# 0_EPS_Interface.net
KiCad netlist of a schematic drawn in Altium Designer
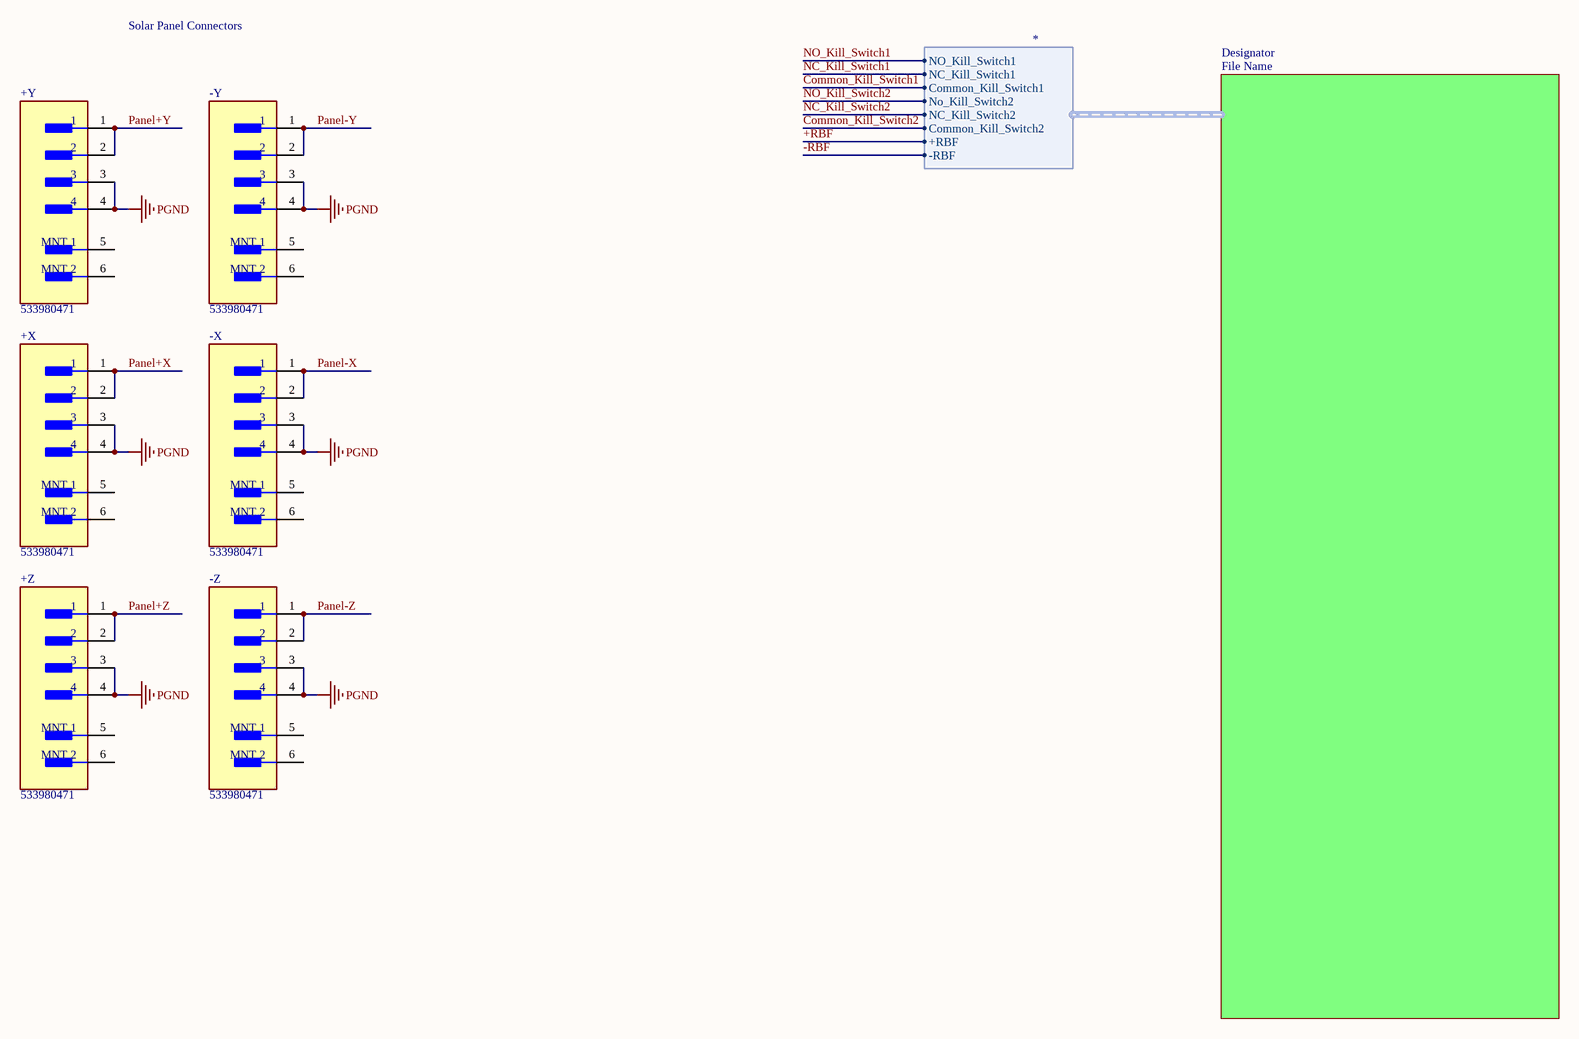
[diagram p0: 0_EPS_Interface.SchDoc]

(export (version "E")
  (design (tool "Eeschema 10.0.6"))
  (components
    (comp (ref "+X")
      (value "533980471")
      (footprint "FP-533980471-MFG")
      (description "Connector Header Surface Mount 4 position 0.049\" (1.25mm)")
      (fields (field (name "OCTOPART") "https://octopart.com/53398-0471-molex-655296"))
      (libsource (lib "Altium Content Vault") (part "3b6f738a5616415d78381ad43816e4a"))
    )
    (comp (ref "+Y")
      (value "533980471")
      (footprint "FP-533980471-MFG")
      (description "Connector Header Surface Mount 4 position 0.049\" (1.25mm)")
      (fields (field (name "OCTOPART") "https://octopart.com/53398-0471-molex-655296"))
      (libsource (lib "Altium Content Vault") (part "3b6f738a5616415d78381ad43816e4a"))
    )
    (comp (ref "+Z")
      (value "533980471")
      (footprint "FP-533980471-MFG")
      (description "Connector Header Surface Mount 4 position 0.049\" (1.25mm)")
      (fields (field (name "OCTOPART") "https://octopart.com/53398-0471-molex-655296"))
      (libsource (lib "Altium Content Vault") (part "3b6f738a5616415d78381ad43816e4a"))
    )
    (comp (ref "-X")
      (value "533980471")
      (footprint "FP-533980471-MFG")
      (description "Connector Header Surface Mount 4 position 0.049\" (1.25mm)")
      (fields (field (name "OCTOPART") "https://octopart.com/53398-0471-molex-655296"))
      (libsource (lib "Altium Content Vault") (part "3b6f738a5616415d78381ad43816e4a"))
    )
    (comp (ref "-Y")
      (value "533980471")
      (footprint "FP-533980471-MFG")
      (description "Connector Header Surface Mount 4 position 0.049\" (1.25mm)")
      (fields (field (name "OCTOPART") "https://octopart.com/53398-0471-molex-655296"))
      (libsource (lib "Altium Content Vault") (part "3b6f738a5616415d78381ad43816e4a"))
    )
    (comp (ref "-Z")
      (value "533980471")
      (footprint "FP-533980471-MFG")
      (description "Connector Header Surface Mount 4 position 0.049\" (1.25mm)")
      (fields (field (name "OCTOPART") "https://octopart.com/53398-0471-molex-655296"))
      (libsource (lib "Altium Content Vault") (part "3b6f738a5616415d78381ad43816e4a"))
    )
  )
  (nets
    (net (code "10") (name "/Panel+X") (class "Default")
      (node (ref "+X") (pin "1") (pinfunction "1_1") (pintype "passive"))
      (node (ref "+X") (pin "2") (pinfunction "2_2") (pintype "passive"))
    )
    (net (code "11") (name "/Panel+Y") (class "Default")
      (node (ref "+Y") (pin "1") (pinfunction "1_1") (pintype "passive"))
      (node (ref "+Y") (pin "2") (pinfunction "2_2") (pintype "passive"))
    )
    (net (code "12") (name "/Panel+Z") (class "Default")
      (node (ref "+Z") (pin "1") (pinfunction "1_1") (pintype "passive"))
      (node (ref "+Z") (pin "2") (pinfunction "2_2") (pintype "passive"))
    )
    (net (code "13") (name "/Panel-X") (class "Default")
      (node (ref "-X") (pin "1") (pinfunction "1_1") (pintype "passive"))
      (node (ref "-X") (pin "2") (pinfunction "2_2") (pintype "passive"))
    )
    (net (code "14") (name "/Panel-Y") (class "Default")
      (node (ref "-Y") (pin "1") (pinfunction "1_1") (pintype "passive"))
      (node (ref "-Y") (pin "2") (pinfunction "2_2") (pintype "passive"))
    )
    (net (code "15") (name "/Panel-Z") (class "Default")
      (node (ref "-Z") (pin "1") (pinfunction "1_1") (pintype "passive"))
      (node (ref "-Z") (pin "2") (pinfunction "2_2") (pintype "passive"))
    )
    (net (code "17") (name "PGND") (class "Default")
      (node (ref "+X") (pin "3") (pinfunction "3_3") (pintype "passive"))
      (node (ref "+X") (pin "4") (pinfunction "4_4") (pintype "passive"))
      (node (ref "+Y") (pin "3") (pinfunction "3_3") (pintype "passive"))
      (node (ref "+Y") (pin "4") (pinfunction "4_4") (pintype "passive"))
      (node (ref "+Z") (pin "3") (pinfunction "3_3") (pintype "passive"))
      (node (ref "+Z") (pin "4") (pinfunction "4_4") (pintype "passive"))
      (node (ref "-X") (pin "3") (pinfunction "3_3") (pintype "passive"))
      (node (ref "-X") (pin "4") (pinfunction "4_4") (pintype "passive"))
      (node (ref "-Y") (pin "3") (pinfunction "3_3") (pintype "passive"))
      (node (ref "-Y") (pin "4") (pinfunction "4_4") (pintype "passive"))
      (node (ref "-Z") (pin "3") (pinfunction "3_3") (pintype "passive"))
      (node (ref "-Z") (pin "4") (pinfunction "4_4") (pintype "passive"))
    )
    (net (code "18") (name "unconnected-(+X-MNT_1-Pad5)") (class "Default")
      (node (ref "+X") (pin "5") (pinfunction "MNT_1_5") (pintype "passive"))
    )
    (net (code "19") (name "unconnected-(+X-MNT_2-Pad6)") (class "Default")
      (node (ref "+X") (pin "6") (pinfunction "MNT_2_6") (pintype "passive"))
    )
    (net (code "20") (name "unconnected-(+Y-MNT_1-Pad5)") (class "Default")
      (node (ref "+Y") (pin "5") (pinfunction "MNT_1_5") (pintype "passive"))
    )
    (net (code "21") (name "unconnected-(+Y-MNT_2-Pad6)") (class "Default")
      (node (ref "+Y") (pin "6") (pinfunction "MNT_2_6") (pintype "passive"))
    )
    (net (code "22") (name "unconnected-(+Z-MNT_1-Pad5)") (class "Default")
      (node (ref "+Z") (pin "5") (pinfunction "MNT_1_5") (pintype "passive"))
    )
    (net (code "23") (name "unconnected-(+Z-MNT_2-Pad6)") (class "Default")
      (node (ref "+Z") (pin "6") (pinfunction "MNT_2_6") (pintype "passive"))
    )
    (net (code "24") (name "unconnected-(-X-MNT_1-Pad5)") (class "Default")
      (node (ref "-X") (pin "5") (pinfunction "MNT_1_5") (pintype "passive"))
    )
    (net (code "25") (name "unconnected-(-X-MNT_2-Pad6)") (class "Default")
      (node (ref "-X") (pin "6") (pinfunction "MNT_2_6") (pintype "passive"))
    )
    (net (code "26") (name "unconnected-(-Y-MNT_1-Pad5)") (class "Default")
      (node (ref "-Y") (pin "5") (pinfunction "MNT_1_5") (pintype "passive"))
    )
    (net (code "27") (name "unconnected-(-Y-MNT_2-Pad6)") (class "Default")
      (node (ref "-Y") (pin "6") (pinfunction "MNT_2_6") (pintype "passive"))
    )
    (net (code "28") (name "unconnected-(-Z-MNT_1-Pad5)") (class "Default")
      (node (ref "-Z") (pin "5") (pinfunction "MNT_1_5") (pintype "passive"))
    )
    (net (code "29") (name "unconnected-(-Z-MNT_2-Pad6)") (class "Default")
      (node (ref "-Z") (pin "6") (pinfunction "MNT_2_6") (pintype "passive"))
    )
  )
)
